# STM32WB55CGU6.net
KiCad netlist of a schematic drawn in Altium Designer
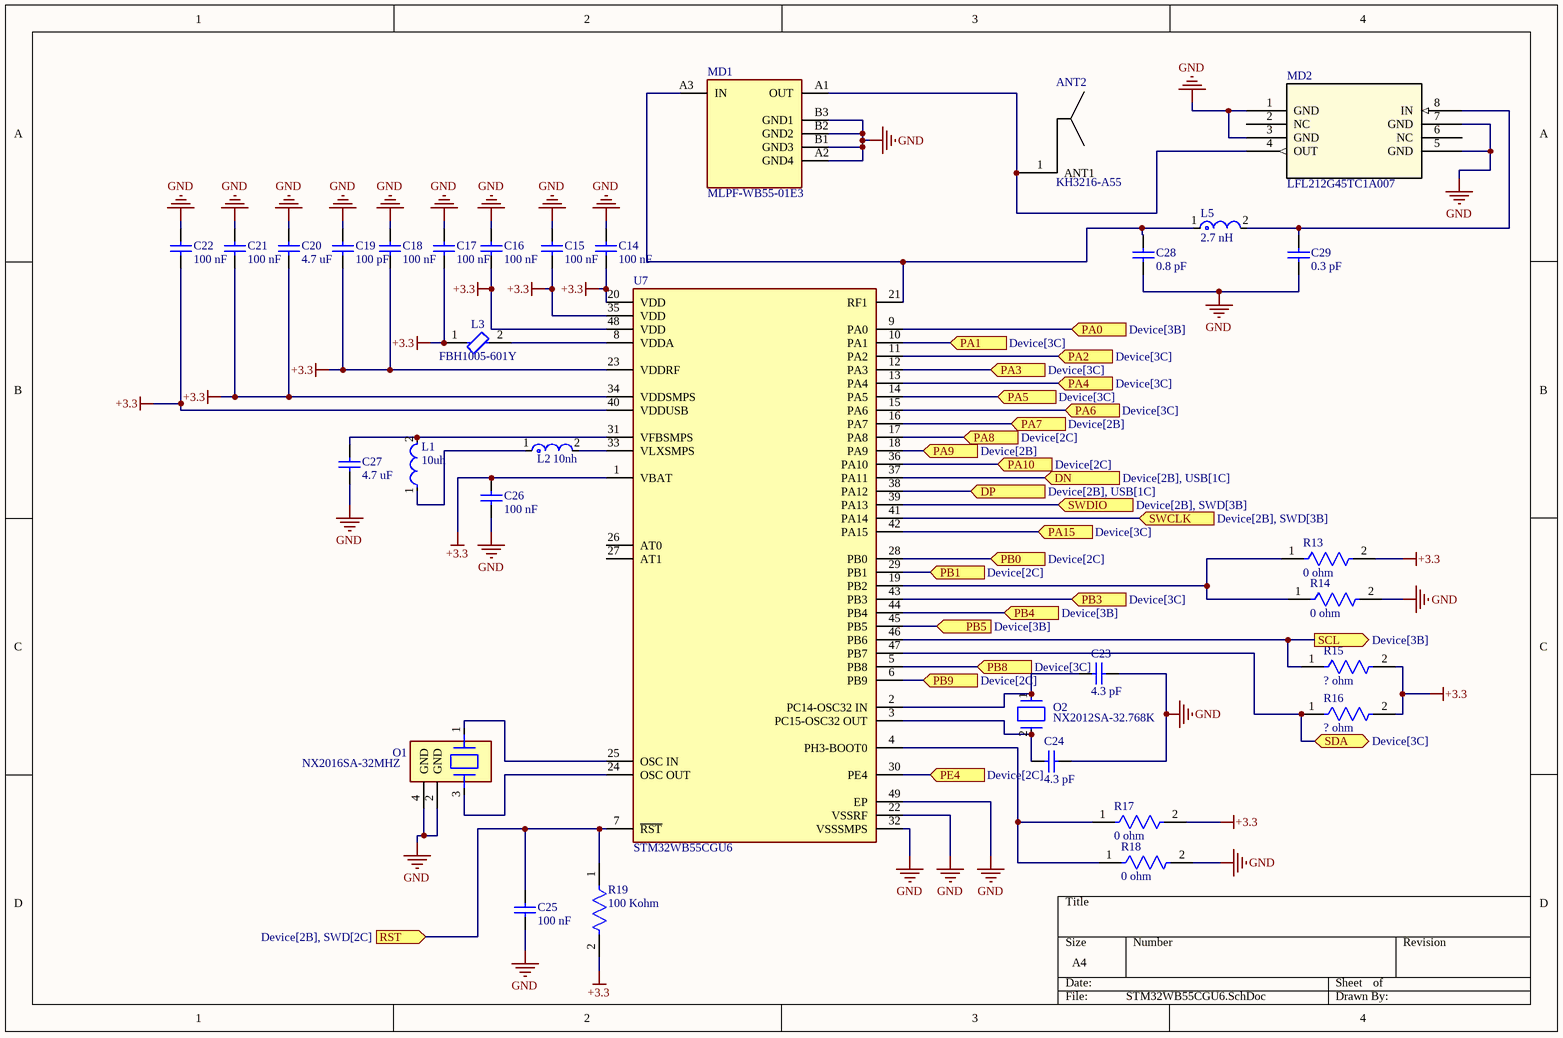
[diagram p0: STM32WB55CGU6.SchDoc]

(export (version "E")
  (design (tool "Eeschema 10.0.6"))
  (components
    (comp (ref "ANT2")
      (value "KH3216-A55")
      (footprint "KH3216-A55")
      (libsource (lib "Custom.") (part "KH3216-A55"))
    )
    (comp (ref "C14")
      (value "100 nF")
      (footprint "CAPC1005X55X25NL05T10")
      (fields (field (name "MANUFACTURER") "Murata") (field (name "PART NUMBER") "GRM155F50J684ZE01D"))
      (libsource (lib "Altium Content Vault") (part "CAP"))
    )
    (comp (ref "C15")
      (value "100 nF")
      (footprint "CAPC1005X55X25NL05T10")
      (fields (field (name "MANUFACTURER") "Murata") (field (name "PART NUMBER") "GRM155F50J684ZE01D"))
      (libsource (lib "Altium Content Vault") (part "CAP"))
    )
    (comp (ref "C16")
      (value "100 nF")
      (footprint "CAPC1005X55X25NL05T10")
      (fields (field (name "MANUFACTURER") "Murata") (field (name "PART NUMBER") "GRM155F50J684ZE01D"))
      (libsource (lib "Altium Content Vault") (part "CAP"))
    )
    (comp (ref "C17")
      (value "100 nF")
      (footprint "CAPC1005X55X25NL05T10")
      (fields (field (name "MANUFACTURER") "Murata") (field (name "PART NUMBER") "GRM155F50J684ZE01D"))
      (libsource (lib "Altium Content Vault") (part "CAP"))
    )
    (comp (ref "C18")
      (value "100 nF")
      (footprint "CAPC1005X55X25NL05T10")
      (fields (field (name "MANUFACTURER") "Murata") (field (name "PART NUMBER") "GRM155F50J684ZE01D"))
      (libsource (lib "Altium Content Vault") (part "CAP"))
    )
    (comp (ref "C19")
      (value "100 pF")
      (footprint "CAPC1005X55X25NL05T10")
      (fields (field (name "MANUFACTURER") "Murata") (field (name "PART NUMBER") "GRM155F50J684ZE01D"))
      (libsource (lib "Altium Content Vault") (part "CAP"))
    )
    (comp (ref "C20")
      (value "4.7 uF")
      (footprint "CAPC1005X55X25NL05T10")
      (fields (field (name "MANUFACTURER") "Murata") (field (name "PART NUMBER") "GRM155F50J684ZE01D"))
      (libsource (lib "Altium Content Vault") (part "CAP"))
    )
    (comp (ref "C21")
      (value "100 nF")
      (footprint "CAPC1005X55X25NL05T10")
      (fields (field (name "MANUFACTURER") "Murata") (field (name "PART NUMBER") "GRM155F50J684ZE01D"))
      (libsource (lib "Altium Content Vault") (part "CAP"))
    )
    (comp (ref "C22")
      (value "100 nF")
      (footprint "CAPC1005X55X25NL05T10")
      (fields (field (name "MANUFACTURER") "Murata") (field (name "PART NUMBER") "GRM155F50J684ZE01D"))
      (libsource (lib "Altium Content Vault") (part "CAP"))
    )
    (comp (ref "C23")
      (value "4.3 pF")
      (footprint "CAPC1005X55X25NL05T10")
      (fields (field (name "MANUFACTURER") "Murata") (field (name "PART NUMBER") "GRM155F50J684ZE01D"))
      (libsource (lib "Altium Content Vault") (part "CAP"))
    )
    (comp (ref "C24")
      (value "4.3 pF")
      (footprint "CAPC1005X55X25NL05T10")
      (fields (field (name "MANUFACTURER") "Murata") (field (name "PART NUMBER") "GRM155F50J684ZE01D"))
      (libsource (lib "Altium Content Vault") (part "CAP"))
    )
    (comp (ref "C25")
      (value "100 nF")
      (footprint "CAPC1005X55X25NL05T10")
      (fields (field (name "MANUFACTURER") "Murata") (field (name "PART NUMBER") "GRM155F50J684ZE01D"))
      (libsource (lib "Altium Content Vault") (part "CAP"))
    )
    (comp (ref "C26")
      (value "100 nF")
      (footprint "CAPC1005X55X25NL05T10")
      (fields (field (name "MANUFACTURER") "Murata") (field (name "PART NUMBER") "GRM155F50J684ZE01D"))
      (libsource (lib "Altium Content Vault") (part "CAP"))
    )
    (comp (ref "C27")
      (value "4.7 uF")
      (footprint "CAPC1005X55X25NL05T10")
      (fields (field (name "MANUFACTURER") "Murata") (field (name "PART NUMBER") "GRM155F50J684ZE01D"))
      (libsource (lib "Altium Content Vault") (part "CAP"))
    )
    (comp (ref "C28")
      (value "0.8 pF")
      (footprint "CAPC1005X55X25NL05T10")
      (fields (field (name "MANUFACTURER") "Murata") (field (name "PART NUMBER") "GRM155F50J684ZE01D"))
      (libsource (lib "Altium Content Vault") (part "CAP"))
    )
    (comp (ref "C29")
      (value "0.3 pF")
      (footprint "CAPC1005X55X25NL05T10")
      (fields (field (name "MANUFACTURER") "Murata") (field (name "PART NUMBER") "GRM155F50J684ZE01D"))
      (libsource (lib "Altium Content Vault") (part "CAP"))
    )
    (comp (ref "L1")
      (value "10uh")
      (footprint "FP-LQM21FN_70-MFG")
      (description "FIXED IND 10UH 100MA 780MOHM SMD")
      (fields (field (name "TOLERANCE") "20%"))
      (libsource (lib "Altium Content Vault") (part "725321dda6339637d4d059423bc1c3c"))
    )
    (comp (ref "L2")
      (value "10nh")
      (footprint "FP-LQG15WH_02-MFG")
      (description "Multilayer type Inductor for Automotive 10nH ±5% 0.19Ω 500mA 0402")
      (fields (field (name "TOLERANCE") "5%"))
      (libsource (lib "Altium Content Vault") (part "4cc4b267dca4c8e51f7102f422741d8"))
    )
    (comp (ref "L3")
      (value "FBH1005-601Y")
      (footprint "FP-BLM15-0_05-MFG")
      (description "Chip Ferrite Bead, 0402, 600Ω @ 100MHz, 0.52Ω, 25%, 300mA")
      (fields (field (name "TOLERANCE") "25%"))
      (libsource (lib "Altium Content Vault") (part "5f30dd21d616792df468990f7003faa"))
    )
    (comp (ref "L5")
      (value "2.7 nH")
      (footprint "FP-LQG15HH_02-IPC_C")
      (description "Multilayer type RF Inductor 2.7nH ±0.3nH 0.12Ω 800mA 0402")
      (libsource (lib "Altium Content Vault") (part "4cc4b267dca4c8e51f7102f422741d8"))
    )
    (comp (ref "MD1")
      (value "MLPF-WB55-01E3")
      (footprint "FP-MLPF-WB55-01E3-MFG")
      (description "RF FILTER LOW PASS 2.45GHZ 6SMD")
      (libsource (lib "Altium Content Vault") (part "51e28da9fe7b2e4e5e03ac85244eada"))
    )
    (comp (ref "MD2")
      (value "LFL212G45TC1A007")
      (footprint "LFL212G45TC1A007")
      (libsource (lib "ReadyButNotListed") (part "LFL212G45TC1A007"))
    )
    (comp (ref "O1")
      (value "NX2016SA-32MHZ")
      (footprint "FP-NX2016SA-MFG")
      (description "CRYSTAL 32.0000MHZ 8PF SMD")
      (libsource (lib "Altium Content Vault") (part "0d11ad3ca7be055efd3b4f344707230"))
    )
    (comp (ref "O2")
      (value "NX2012SA-32.768K")
      (footprint "FP-NX2012SA-MFG")
      (description "CRYSTAL 32.7680KHZ 12.5PF SMD")
      (libsource (lib "Altium Content Vault") (part "c23a69dc6c9e2f18f2079038eb95dd1"))
    )
    (comp (ref "R13")
      (value "0 ohm")
      (footprint "FP-RC1005-IPC_C")
      (description "Res Thick Film 0402 1.87kΩ 1% 0.063W ±100ppm/°C Molded SMD T/R")
      (fields (field (name "TOLERANCE") "1%"))
      (libsource (lib "Altium Content Vault") (part "1029c3af85768c4190bb7ad29bc67b5"))
    )
    (comp (ref "R14")
      (value "0 ohm")
      (footprint "FP-RC1005-IPC_C")
      (description "Res Thick Film 0402 1.87kΩ 1% 0.063W ±100ppm/°C Molded SMD T/R")
      (fields (field (name "TOLERANCE") "1%"))
      (libsource (lib "Altium Content Vault") (part "1029c3af85768c4190bb7ad29bc67b5"))
    )
    (comp (ref "R15")
      (value "? ohm")
      (footprint "FP-RC1005-IPC_C")
      (description "Res Thick Film 0402 1.87kΩ 1% 0.063W ±100ppm/°C Molded SMD T/R")
      (fields (field (name "TOLERANCE") "1%"))
      (libsource (lib "Altium Content Vault") (part "1029c3af85768c4190bb7ad29bc67b5"))
    )
    (comp (ref "R16")
      (value "? ohm")
      (footprint "FP-RC1005-IPC_C")
      (description "Res Thick Film 0402 1.87kΩ 1% 0.063W ±100ppm/°C Molded SMD T/R")
      (fields (field (name "TOLERANCE") "1%"))
      (libsource (lib "Altium Content Vault") (part "1029c3af85768c4190bb7ad29bc67b5"))
    )
    (comp (ref "R17")
      (value "0 ohm")
      (footprint "FP-RC1005-IPC_C")
      (description "Res Thick Film 0402 1.87kΩ 1% 0.063W ±100ppm/°C Molded SMD T/R")
      (fields (field (name "TOLERANCE") "1%"))
      (libsource (lib "Altium Content Vault") (part "1029c3af85768c4190bb7ad29bc67b5"))
    )
    (comp (ref "R18")
      (value "0 ohm")
      (footprint "FP-RC1005-IPC_C")
      (description "Res Thick Film 0402 1.87kΩ 1% 0.063W ±100ppm/°C Molded SMD T/R")
      (fields (field (name "TOLERANCE") "1%"))
      (libsource (lib "Altium Content Vault") (part "1029c3af85768c4190bb7ad29bc67b5"))
    )
    (comp (ref "R19")
      (value "100 Kohm")
      (footprint "FP-RC1005-IPC_C")
      (description "Res Thick Film 0402 1.87kΩ 1% 0.063W ±100ppm/°C Molded SMD T/R")
      (fields (field (name "TOLERANCE") "1%"))
      (libsource (lib "Altium Content Vault") (part "1029c3af85768c4190bb7ad29bc67b5"))
    )
    (comp (ref "U7")
      (value "STM32WB55CGU6")
      (footprint "FP-STM32WB55CGU6-MFG")
      (description "ULTRA-LOW-POWER DUAL CORE ARM CO")
      (fields
        (field (name "OCTOPART") "https://octopart.com/stm32wb55cgu6-stmicroelectronics-98750847")
        (field (name "MANUFACTURER") "STMicroelectronics")
      )
      (libsource (lib "Altium Content Vault") (part "9d9ca7f3567da95c474f3f549f05e68"))
    )
  )
  (nets
    (net (code "1") (name "+3.3") (class "Default")
      (node (ref "C14") (pin "1") (pinfunction "1_1") (pintype "passive"))
      (node (ref "C15") (pin "2") (pinfunction "2_2") (pintype "passive"))
      (node (ref "C16") (pin "1") (pinfunction "1_1") (pintype "passive"))
      (node (ref "C17") (pin "2") (pinfunction "2_2") (pintype "passive"))
      (node (ref "C18") (pin "1") (pinfunction "1_1") (pintype "passive"))
      (node (ref "C19") (pin "2") (pinfunction "2_2") (pintype "passive"))
      (node (ref "C20") (pin "2") (pinfunction "2_2") (pintype "passive"))
      (node (ref "C21") (pin "1") (pinfunction "1_1") (pintype "passive"))
      (node (ref "C22") (pin "2") (pinfunction "2_2") (pintype "passive"))
      (node (ref "C26") (pin "2") (pinfunction "2_2") (pintype "passive"))
      (node (ref "L3") (pin "1") (pinfunction "1_1") (pintype "passive"))
      (node (ref "R13") (pin "2") (pinfunction "2_2") (pintype "passive"))
      (node (ref "R15") (pin "2") (pinfunction "2_2") (pintype "passive"))
      (node (ref "R16") (pin "2") (pinfunction "2_2") (pintype "passive"))
      (node (ref "R17") (pin "2") (pinfunction "2_2") (pintype "passive"))
      (node (ref "R19") (pin "2") (pinfunction "2_2") (pintype "passive"))
      (node (ref "U7") (pin "1") (pinfunction "VBAT_1") (pintype "passive"))
      (node (ref "U7") (pin "20") (pinfunction "VDD_20") (pintype "passive"))
      (node (ref "U7") (pin "23") (pinfunction "VDDRF_23") (pintype "passive"))
      (node (ref "U7") (pin "34") (pinfunction "VDDSMPS_34") (pintype "passive"))
      (node (ref "U7") (pin "35") (pinfunction "VDD_35") (pintype "passive"))
      (node (ref "U7") (pin "40") (pinfunction "VDDUSB_40") (pintype "passive"))
      (node (ref "U7") (pin "48") (pinfunction "VDD_48") (pintype "passive"))
    )
    (net (code "2") (name "/DN") (class "Default")
      (node (ref "U7") (pin "37") (pinfunction "PA11_37") (pintype "passive"))
    )
    (net (code "3") (name "/DP") (class "Default")
      (node (ref "U7") (pin "38") (pinfunction "PA12_38") (pintype "passive"))
    )
    (net (code "4") (name "/PA0") (class "Default")
      (node (ref "U7") (pin "9") (pinfunction "PA0_9") (pintype "passive"))
    )
    (net (code "5") (name "/PA1") (class "Default")
      (node (ref "U7") (pin "10") (pinfunction "PA1_10") (pintype "passive"))
    )
    (net (code "6") (name "/PA2") (class "Default")
      (node (ref "U7") (pin "11") (pinfunction "PA2_11") (pintype "passive"))
    )
    (net (code "7") (name "/PA3") (class "Default")
      (node (ref "U7") (pin "12") (pinfunction "PA3_12") (pintype "passive"))
    )
    (net (code "8") (name "/PA4") (class "Default")
      (node (ref "U7") (pin "13") (pinfunction "PA4_13") (pintype "passive"))
    )
    (net (code "9") (name "/PA5") (class "Default")
      (node (ref "U7") (pin "14") (pinfunction "PA5_14") (pintype "passive"))
    )
    (net (code "10") (name "/PA6") (class "Default")
      (node (ref "U7") (pin "15") (pinfunction "PA6_15") (pintype "passive"))
    )
    (net (code "11") (name "/PA7") (class "Default")
      (node (ref "U7") (pin "16") (pinfunction "PA7_16") (pintype "passive"))
    )
    (net (code "12") (name "/PA8") (class "Default")
      (node (ref "U7") (pin "17") (pinfunction "PA8_17") (pintype "passive"))
    )
    (net (code "13") (name "/PA9") (class "Default")
      (node (ref "U7") (pin "18") (pinfunction "PA9_18") (pintype "passive"))
    )
    (net (code "14") (name "/PA10") (class "Default")
      (node (ref "U7") (pin "36") (pinfunction "PA10_36") (pintype "passive"))
    )
    (net (code "15") (name "/PA15") (class "Default")
      (node (ref "U7") (pin "42") (pinfunction "PA15_42") (pintype "passive"))
    )
    (net (code "16") (name "/PB0") (class "Default")
      (node (ref "U7") (pin "28") (pinfunction "PB0_28") (pintype "passive"))
    )
    (net (code "17") (name "/PB1") (class "Default")
      (node (ref "U7") (pin "29") (pinfunction "PB1_29") (pintype "passive"))
    )
    (net (code "18") (name "/PB3") (class "Default")
      (node (ref "U7") (pin "43") (pinfunction "PB3_43") (pintype "passive"))
    )
    (net (code "19") (name "/PB4") (class "Default")
      (node (ref "U7") (pin "44") (pinfunction "PB4_44") (pintype "passive"))
    )
    (net (code "20") (name "/PB5") (class "Default")
      (node (ref "U7") (pin "45") (pinfunction "PB5_45") (pintype "passive"))
    )
    (net (code "21") (name "/PB8") (class "Default")
      (node (ref "U7") (pin "5") (pinfunction "PB8_5") (pintype "passive"))
    )
    (net (code "22") (name "/PB9") (class "Default")
      (node (ref "U7") (pin "6") (pinfunction "PB9_6") (pintype "passive"))
    )
    (net (code "23") (name "/PE4") (class "Default")
      (node (ref "U7") (pin "30") (pinfunction "PE4_30") (pintype "passive"))
    )
    (net (code "24") (name "/RST") (class "Default")
      (node (ref "C25") (pin "2") (pinfunction "2_2") (pintype "passive"))
      (node (ref "R19") (pin "1") (pinfunction "1_1") (pintype "passive"))
      (node (ref "U7") (pin "7") (pinfunction "~{RST}_7") (pintype "passive"))
    )
    (net (code "25") (name "/SCL") (class "Default")
      (node (ref "R15") (pin "1") (pinfunction "1_1") (pintype "passive"))
      (node (ref "U7") (pin "46") (pinfunction "PB6_46") (pintype "passive"))
    )
    (net (code "26") (name "/SDA") (class "Default")
      (node (ref "R16") (pin "1") (pinfunction "1_1") (pintype "passive"))
      (node (ref "U7") (pin "47") (pinfunction "PB7_47") (pintype "passive"))
    )
    (net (code "27") (name "/SWCLK") (class "Default")
      (node (ref "U7") (pin "41") (pinfunction "PA14_41") (pintype "passive"))
    )
    (net (code "28") (name "/SWDIO") (class "Default")
      (node (ref "U7") (pin "39") (pinfunction "PA13_39") (pintype "passive"))
    )
    (net (code "29") (name "GND") (class "Default")
      (node (ref "C14") (pin "2") (pinfunction "2_2") (pintype "passive"))
      (node (ref "C15") (pin "1") (pinfunction "1_1") (pintype "passive"))
      (node (ref "C16") (pin "2") (pinfunction "2_2") (pintype "passive"))
      (node (ref "C17") (pin "1") (pinfunction "1_1") (pintype "passive"))
      (node (ref "C18") (pin "2") (pinfunction "2_2") (pintype "passive"))
      (node (ref "C19") (pin "1") (pinfunction "1_1") (pintype "passive"))
      (node (ref "C20") (pin "1") (pinfunction "1_1") (pintype "passive"))
      (node (ref "C21") (pin "2") (pinfunction "2_2") (pintype "passive"))
      (node (ref "C22") (pin "1") (pinfunction "1_1") (pintype "passive"))
      (node (ref "C23") (pin "2") (pinfunction "2_2") (pintype "passive"))
      (node (ref "C24") (pin "1") (pinfunction "1_1") (pintype "passive"))
      (node (ref "C25") (pin "1") (pinfunction "1_1") (pintype "passive"))
      (node (ref "C26") (pin "1") (pinfunction "1_1") (pintype "passive"))
      (node (ref "C27") (pin "2") (pinfunction "2_2") (pintype "passive"))
      (node (ref "C28") (pin "2") (pinfunction "2_2") (pintype "passive"))
      (node (ref "C29") (pin "2") (pinfunction "2_2") (pintype "passive"))
      (node (ref "MD1") (pin "A2") (pinfunction "GND4_A2") (pintype "power_in"))
      (node (ref "MD1") (pin "B1") (pinfunction "GND3_B1") (pintype "power_in"))
      (node (ref "MD1") (pin "B2") (pinfunction "GND2_B2") (pintype "power_in"))
      (node (ref "MD1") (pin "B3") (pinfunction "GND1_B3") (pintype "power_in"))
      (node (ref "MD2") (pin "1") (pinfunction "GND_1") (pintype "passive"))
      (node (ref "MD2") (pin "3") (pinfunction "GND_3") (pintype "passive"))
      (node (ref "MD2") (pin "5") (pinfunction "GND_5") (pintype "passive"))
      (node (ref "MD2") (pin "7") (pinfunction "GND_7") (pintype "passive"))
      (node (ref "O1") (pin "2") (pinfunction "GND_2") (pintype "power_in"))
      (node (ref "O1") (pin "4") (pinfunction "GND_4") (pintype "power_in"))
      (node (ref "R14") (pin "2") (pinfunction "2_2") (pintype "passive"))
      (node (ref "R18") (pin "2") (pinfunction "2_2") (pintype "passive"))
      (node (ref "U7") (pin "22") (pinfunction "VSSRF_22") (pintype "passive"))
      (node (ref "U7") (pin "32") (pinfunction "VSSSMPS_32") (pintype "passive"))
      (node (ref "U7") (pin "49") (pinfunction "EP_49") (pintype "power_in"))
    )
    (net (code "30") (name "Net-(ANT2-ANT1)") (class "Default")
      (node (ref "ANT2") (pin "1") (pinfunction "ANT1_1") (pintype "passive"))
      (node (ref "MD1") (pin "A1") (pinfunction "OUT_A1") (pintype "passive"))
      (node (ref "MD2") (pin "4") (pinfunction "OUT_4") (pintype "output"))
    )
    (net (code "31") (name "Net-(L1-Pad1)") (class "Default")
      (node (ref "L1") (pin "1") (pinfunction "1_1") (pintype "passive"))
      (node (ref "L2") (pin "1") (pinfunction "1_1") (pintype "passive"))
    )
    (net (code "32") (name "Net-(MD1-IN)") (class "Default")
      (node (ref "C28") (pin "1") (pinfunction "1_1") (pintype "passive"))
      (node (ref "L5") (pin "1") (pinfunction "1_1") (pintype "passive"))
      (node (ref "MD1") (pin "A3") (pinfunction "IN_A3") (pintype "power_in"))
      (node (ref "U7") (pin "21") (pinfunction "RF1_21") (pintype "passive"))
    )
    (net (code "33") (name "Net-(MD2-IN)") (class "Default")
      (node (ref "C29") (pin "1") (pinfunction "1_1") (pintype "passive"))
      (node (ref "L5") (pin "2") (pinfunction "2_2") (pintype "passive"))
      (node (ref "MD2") (pin "8") (pinfunction "IN_8") (pintype "input"))
    )
    (net (code "34") (name "Net-(U7-OSC_IN)") (class "Default")
      (node (ref "O1") (pin "1") (pinfunction "1_1") (pintype "passive"))
      (node (ref "U7") (pin "25") (pinfunction "OSC_IN_25") (pintype "passive"))
    )
    (net (code "35") (name "Net-(U7-OSC_OUT)") (class "Default")
      (node (ref "O1") (pin "3") (pinfunction "3_3") (pintype "passive"))
      (node (ref "U7") (pin "24") (pinfunction "OSC_OUT_24") (pintype "passive"))
    )
    (net (code "36") (name "Net-(U7-PB2)") (class "Default")
      (node (ref "R13") (pin "1") (pinfunction "1_1") (pintype "passive"))
      (node (ref "R14") (pin "1") (pinfunction "1_1") (pintype "passive"))
      (node (ref "U7") (pin "19") (pinfunction "PB2_19") (pintype "passive"))
    )
    (net (code "37") (name "Net-(U7-PC14-OSC32_IN)") (class "Default")
      (node (ref "C23") (pin "1") (pinfunction "1_1") (pintype "passive"))
      (node (ref "O2") (pin "1") (pinfunction "1_1") (pintype "passive"))
      (node (ref "U7") (pin "2") (pinfunction "PC14-OSC32_IN_2") (pintype "passive"))
    )
    (net (code "38") (name "Net-(U7-PC15-OSC32_OUT)") (class "Default")
      (node (ref "C24") (pin "2") (pinfunction "2_2") (pintype "passive"))
      (node (ref "O2") (pin "2") (pinfunction "2_2") (pintype "passive"))
      (node (ref "U7") (pin "3") (pinfunction "PC15-OSC32_OUT_3") (pintype "passive"))
    )
    (net (code "39") (name "Net-(U7-PH3-BOOT0)") (class "Default")
      (node (ref "R17") (pin "1") (pinfunction "1_1") (pintype "passive"))
      (node (ref "R18") (pin "1") (pinfunction "1_1") (pintype "passive"))
      (node (ref "U7") (pin "4") (pinfunction "PH3-BOOT0_4") (pintype "passive"))
    )
    (net (code "40") (name "Net-(U7-VDDA)") (class "Default")
      (node (ref "L3") (pin "2") (pinfunction "2_2") (pintype "passive"))
      (node (ref "U7") (pin "8") (pinfunction "VDDA_8") (pintype "passive"))
    )
    (net (code "41") (name "Net-(U7-VFBSMPS)") (class "Default")
      (node (ref "C27") (pin "1") (pinfunction "1_1") (pintype "passive"))
      (node (ref "L1") (pin "2") (pinfunction "2_2") (pintype "passive"))
      (node (ref "U7") (pin "31") (pinfunction "VFBSMPS_31") (pintype "passive"))
    )
    (net (code "42") (name "Net-(U7-VLXSMPS)") (class "Default")
      (node (ref "L2") (pin "2") (pinfunction "2_2") (pintype "passive"))
      (node (ref "U7") (pin "33") (pinfunction "VLXSMPS_33") (pintype "passive"))
    )
    (net (code "43") (name "unconnected-(MD2-NC-Pad2)") (class "Default")
      (node (ref "MD2") (pin "2") (pinfunction "NC_2") (pintype "passive"))
    )
    (net (code "44") (name "unconnected-(MD2-NC-Pad6)") (class "Default")
      (node (ref "MD2") (pin "6") (pinfunction "NC_6") (pintype "passive"))
    )
    (net (code "45") (name "unconnected-(U7-AT0-Pad26)") (class "Default")
      (node (ref "U7") (pin "26") (pinfunction "AT0_26") (pintype "passive"))
    )
    (net (code "46") (name "unconnected-(U7-AT1-Pad27)") (class "Default")
      (node (ref "U7") (pin "27") (pinfunction "AT1_27") (pintype "passive"))
    )
  )
)
